# as_wounds_switches.net
KiCad netlist of a schematic drawn in EAGLE
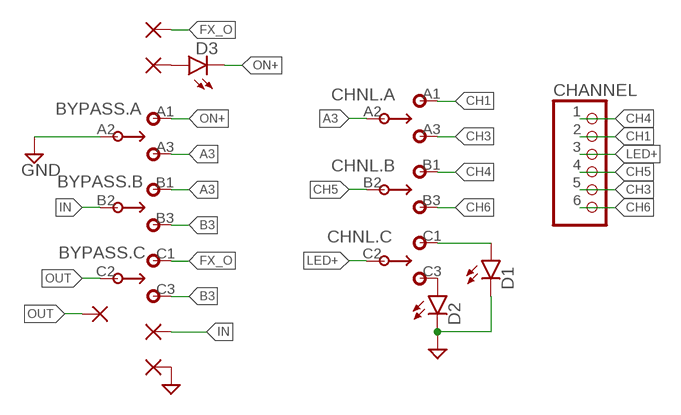
[diagram p0: schematic, sheet 1]

(export (version "E")
  (design (tool "Eeschema 10.0.6"))
  (components
    (comp (ref "BYPASS")
      (value "3PDT.LUGS")
      (footprint "eagle-import:3PDT.LUGS")
      (libsource (lib "eagle-import") (part "3PDT.LUGS"))
    )
    (comp (ref "CHANNEL")
      (value "PINHD-1X6")
      (footprint "eagle-import:1X06")
      (libsource (lib "eagle-import") (part "PINHD-1X6"))
    )
    (comp (ref "CHNL")
      (value "3PDT.LUGS")
      (footprint "eagle-import:3PDT.LUGS")
      (libsource (lib "eagle-import") (part "3PDT.LUGS"))
    )
    (comp (ref "D1")
      (value "LED.1")
      (footprint "eagle-import:3MM_IO")
      (libsource (lib "eagle-import") (part "LED.1"))
    )
    (comp (ref "D2")
      (value "LED.1")
      (footprint "eagle-import:3MM_IO")
      (libsource (lib "eagle-import") (part "LED.1"))
    )
    (comp (ref "D3")
      (value "LED.1")
      (footprint "eagle-import:3MM_IO")
      (libsource (lib "eagle-import") (part "LED.1"))
    )
    (comp (ref "PAD1")
      (value "1,6/0,8")
      (footprint "eagle-import:1,6_0,8")
      (libsource (lib "eagle-import") (part "1,6/0,8"))
    )
    (comp (ref "PAD2")
      (value "1,6/0,8")
      (footprint "eagle-import:1,6_0,8")
      (libsource (lib "eagle-import") (part "1,6/0,8"))
    )
    (comp (ref "PAD3")
      (value "1,6/0,8")
      (footprint "eagle-import:1,6_0,8")
      (libsource (lib "eagle-import") (part "1,6/0,8"))
    )
    (comp (ref "PAD4")
      (value "1,6/0,8")
      (footprint "eagle-import:1,6_0,8")
      (libsource (lib "eagle-import") (part "1,6/0,8"))
    )
    (comp (ref "PAD5")
      (value "1,6/0,8")
      (footprint "eagle-import:1,6_0,8")
      (libsource (lib "eagle-import") (part "1,6/0,8"))
    )
  )
  (nets
    (net (code "1") (name "A3") (class "Default")
      (node (ref "BYPASS") (pin "A3") (pinfunction "3_A3") (pintype "passive"))
      (node (ref "BYPASS") (pin "B1") (pinfunction "1_B1") (pintype "passive"))
      (node (ref "CHNL") (pin "A2") (pinfunction "2_A2") (pintype "passive"))
    )
    (net (code "2") (name "B3") (class "Default")
      (node (ref "BYPASS") (pin "B3") (pinfunction "3_B3") (pintype "passive"))
      (node (ref "BYPASS") (pin "C3") (pinfunction "3_C3") (pintype "passive"))
    )
    (net (code "3") (name "CH1") (class "Default")
      (node (ref "CHANNEL") (pin "2") (pinfunction "2_2") (pintype "passive"))
      (node (ref "CHNL") (pin "A1") (pinfunction "1_A1") (pintype "passive"))
    )
    (net (code "4") (name "CH3") (class "Default")
      (node (ref "CHANNEL") (pin "5") (pinfunction "5_5") (pintype "passive"))
      (node (ref "CHNL") (pin "A3") (pinfunction "3_A3") (pintype "passive"))
    )
    (net (code "5") (name "CH4") (class "Default")
      (node (ref "CHANNEL") (pin "1") (pinfunction "1_1") (pintype "passive"))
      (node (ref "CHNL") (pin "B1") (pinfunction "1_B1") (pintype "passive"))
    )
    (net (code "6") (name "CH5") (class "Default")
      (node (ref "CHANNEL") (pin "4") (pinfunction "4_4") (pintype "passive"))
      (node (ref "CHNL") (pin "B2") (pinfunction "2_B2") (pintype "passive"))
    )
    (net (code "7") (name "CH6") (class "Default")
      (node (ref "CHANNEL") (pin "6") (pinfunction "6_6") (pintype "passive"))
      (node (ref "CHNL") (pin "B3") (pinfunction "3_B3") (pintype "passive"))
    )
    (net (code "8") (name "FX_O") (class "Default")
      (node (ref "BYPASS") (pin "C1") (pinfunction "1_C1") (pintype "passive"))
      (node (ref "PAD1") (pin "1") (pinfunction "P_1") (pintype "passive"))
    )
    (net (code "9") (name "GND") (class "Default")
      (node (ref "BYPASS") (pin "A2") (pinfunction "2_A2") (pintype "passive"))
      (node (ref "D1") (pin "K") (pinfunction "C_K") (pintype "passive"))
      (node (ref "D2") (pin "K") (pinfunction "C_K") (pintype "passive"))
      (node (ref "PAD4") (pin "1") (pinfunction "P_1") (pintype "passive"))
    )
    (net (code "10") (name "IN") (class "Default")
      (node (ref "BYPASS") (pin "B2") (pinfunction "2_B2") (pintype "passive"))
      (node (ref "PAD3") (pin "1") (pinfunction "P_1") (pintype "passive"))
    )
    (net (code "11") (name "LED+") (class "Default")
      (node (ref "CHANNEL") (pin "3") (pinfunction "3_3") (pintype "passive"))
      (node (ref "CHNL") (pin "C2") (pinfunction "2_C2") (pintype "passive"))
    )
    (net (code "12") (name "Net-(CHNLC-1)") (class "Default")
      (node (ref "CHNL") (pin "C1") (pinfunction "1_C1") (pintype "passive"))
      (node (ref "D1") (pin "A") (pinfunction "A_A") (pintype "passive"))
    )
    (net (code "13") (name "Net-(CHNLC-3)") (class "Default")
      (node (ref "CHNL") (pin "C3") (pinfunction "3_C3") (pintype "passive"))
      (node (ref "D2") (pin "A") (pinfunction "A_A") (pintype "passive"))
    )
    (net (code "14") (name "Net-(PAD2-P)") (class "Default")
      (node (ref "D3") (pin "A") (pinfunction "A_A") (pintype "passive"))
      (node (ref "PAD2") (pin "1") (pinfunction "P_1") (pintype "passive"))
    )
    (net (code "15") (name "ON+") (class "Default")
      (node (ref "BYPASS") (pin "A1") (pinfunction "1_A1") (pintype "passive"))
      (node (ref "D3") (pin "K") (pinfunction "C_K") (pintype "passive"))
    )
    (net (code "16") (name "OUT") (class "Default")
      (node (ref "BYPASS") (pin "C2") (pinfunction "2_C2") (pintype "passive"))
      (node (ref "PAD5") (pin "1") (pinfunction "P_1") (pintype "passive"))
    )
  )
)
